# LED16_23.net
KiCad netlist of a schematic drawn in Altium Designer
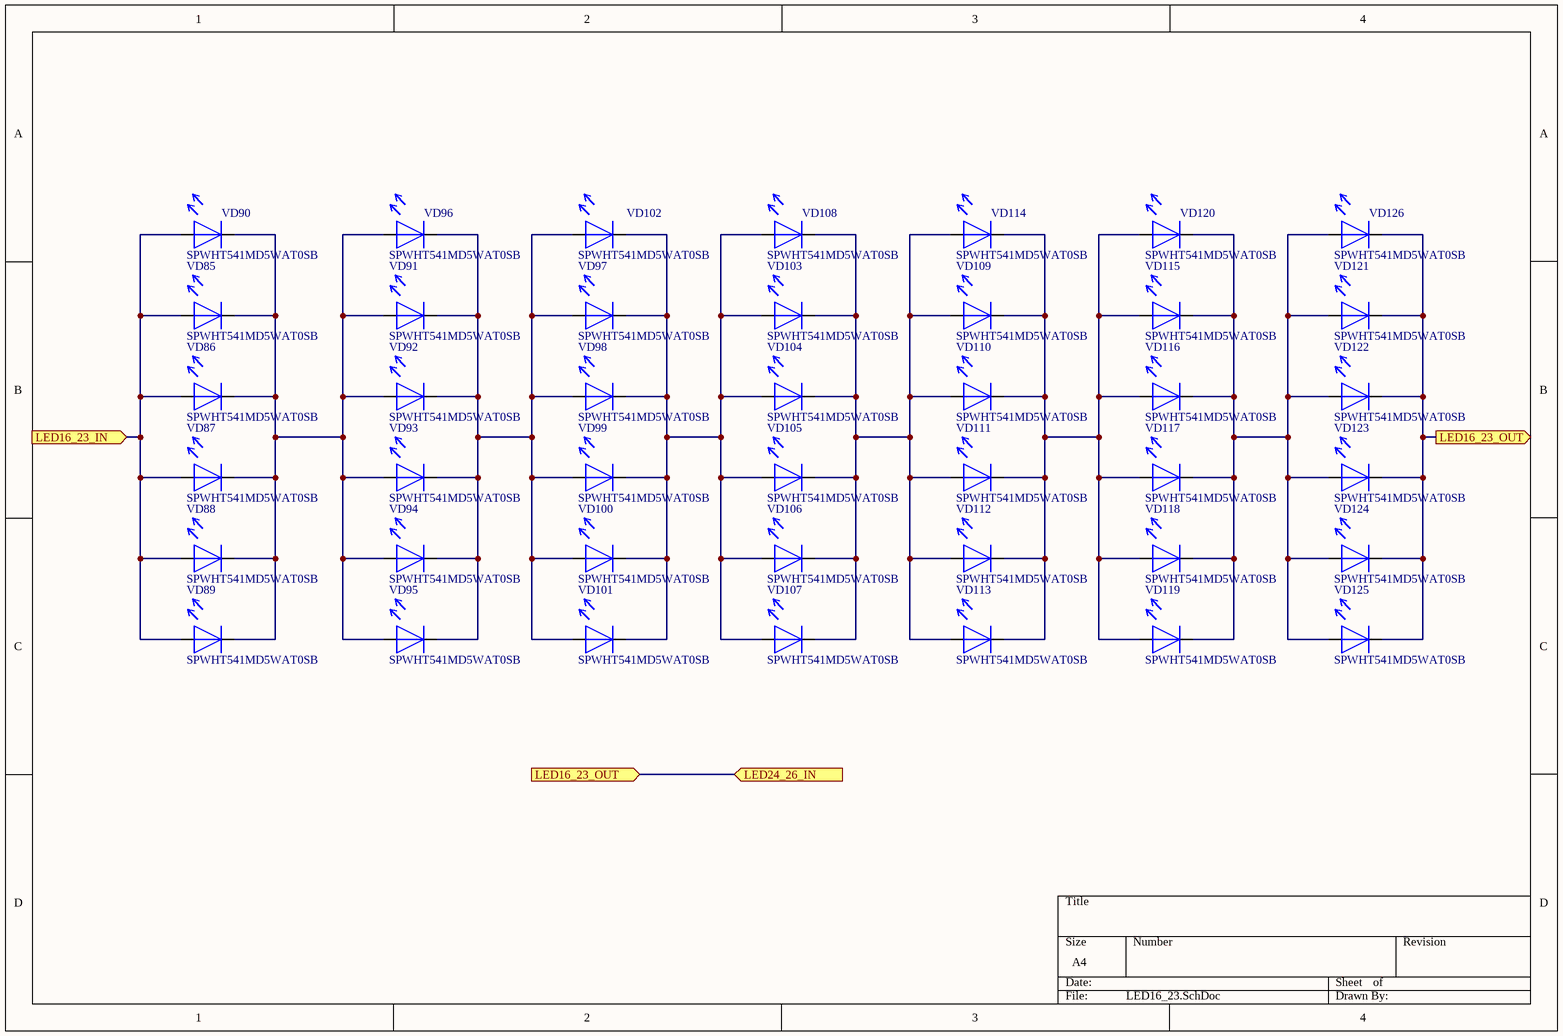
[diagram p0: LED16_23.SchDoc]

(export (version "E")
  (design (tool "Eeschema 10.0.6"))
  (components
    (comp (ref "VD85")
      (value "SPWHT541MD5WAT0SB")
      (footprint "LED_SAMSUNG")
      (libsource (lib "gprs_modem") (part "LED SPWHT541MD5WAT0SB"))
    )
    (comp (ref "VD86")
      (value "SPWHT541MD5WAT0SB")
      (footprint "LED_SAMSUNG")
      (libsource (lib "gprs_modem") (part "LED SPWHT541MD5WAT0SB"))
    )
    (comp (ref "VD87")
      (value "SPWHT541MD5WAT0SB")
      (footprint "LED_SAMSUNG")
      (libsource (lib "gprs_modem") (part "LED SPWHT541MD5WAT0SB"))
    )
    (comp (ref "VD88")
      (value "SPWHT541MD5WAT0SB")
      (footprint "LED_SAMSUNG")
      (libsource (lib "gprs_modem") (part "LED SPWHT541MD5WAT0SB"))
    )
    (comp (ref "VD89")
      (value "SPWHT541MD5WAT0SB")
      (footprint "LED_SAMSUNG")
      (libsource (lib "gprs_modem") (part "LED SPWHT541MD5WAT0SB"))
    )
    (comp (ref "VD90")
      (value "SPWHT541MD5WAT0SB")
      (footprint "LED_SAMSUNG")
      (libsource (lib "gprs_modem") (part "LED SPWHT541MD5WAT0SB"))
    )
    (comp (ref "VD91")
      (value "SPWHT541MD5WAT0SB")
      (footprint "LED_SAMSUNG")
      (libsource (lib "gprs_modem") (part "LED SPWHT541MD5WAT0SB"))
    )
    (comp (ref "VD92")
      (value "SPWHT541MD5WAT0SB")
      (footprint "LED_SAMSUNG")
      (libsource (lib "gprs_modem") (part "LED SPWHT541MD5WAT0SB"))
    )
    (comp (ref "VD93")
      (value "SPWHT541MD5WAT0SB")
      (footprint "LED_SAMSUNG")
      (libsource (lib "gprs_modem") (part "LED SPWHT541MD5WAT0SB"))
    )
    (comp (ref "VD94")
      (value "SPWHT541MD5WAT0SB")
      (footprint "LED_SAMSUNG")
      (libsource (lib "gprs_modem") (part "LED SPWHT541MD5WAT0SB"))
    )
    (comp (ref "VD95")
      (value "SPWHT541MD5WAT0SB")
      (footprint "LED_SAMSUNG")
      (libsource (lib "gprs_modem") (part "LED SPWHT541MD5WAT0SB"))
    )
    (comp (ref "VD96")
      (value "SPWHT541MD5WAT0SB")
      (footprint "LED_SAMSUNG")
      (libsource (lib "gprs_modem") (part "LED SPWHT541MD5WAT0SB"))
    )
    (comp (ref "VD97")
      (value "SPWHT541MD5WAT0SB")
      (footprint "LED_SAMSUNG")
      (libsource (lib "gprs_modem") (part "LED SPWHT541MD5WAT0SB"))
    )
    (comp (ref "VD98")
      (value "SPWHT541MD5WAT0SB")
      (footprint "LED_SAMSUNG")
      (libsource (lib "gprs_modem") (part "LED SPWHT541MD5WAT0SB"))
    )
    (comp (ref "VD99")
      (value "SPWHT541MD5WAT0SB")
      (footprint "LED_SAMSUNG")
      (libsource (lib "gprs_modem") (part "LED SPWHT541MD5WAT0SB"))
    )
    (comp (ref "VD100")
      (value "SPWHT541MD5WAT0SB")
      (footprint "LED_SAMSUNG")
      (libsource (lib "gprs_modem") (part "LED SPWHT541MD5WAT0SB"))
    )
    (comp (ref "VD101")
      (value "SPWHT541MD5WAT0SB")
      (footprint "LED_SAMSUNG")
      (libsource (lib "gprs_modem") (part "LED SPWHT541MD5WAT0SB"))
    )
    (comp (ref "VD102")
      (value "SPWHT541MD5WAT0SB")
      (footprint "LED_SAMSUNG")
      (libsource (lib "gprs_modem") (part "LED SPWHT541MD5WAT0SB"))
    )
    (comp (ref "VD103")
      (value "SPWHT541MD5WAT0SB")
      (footprint "LED_SAMSUNG")
      (libsource (lib "gprs_modem") (part "LED SPWHT541MD5WAT0SB"))
    )
    (comp (ref "VD104")
      (value "SPWHT541MD5WAT0SB")
      (footprint "LED_SAMSUNG")
      (libsource (lib "gprs_modem") (part "LED SPWHT541MD5WAT0SB"))
    )
    (comp (ref "VD105")
      (value "SPWHT541MD5WAT0SB")
      (footprint "LED_SAMSUNG")
      (libsource (lib "gprs_modem") (part "LED SPWHT541MD5WAT0SB"))
    )
    (comp (ref "VD106")
      (value "SPWHT541MD5WAT0SB")
      (footprint "LED_SAMSUNG")
      (libsource (lib "gprs_modem") (part "LED SPWHT541MD5WAT0SB"))
    )
    (comp (ref "VD107")
      (value "SPWHT541MD5WAT0SB")
      (footprint "LED_SAMSUNG")
      (libsource (lib "gprs_modem") (part "LED SPWHT541MD5WAT0SB"))
    )
    (comp (ref "VD108")
      (value "SPWHT541MD5WAT0SB")
      (footprint "LED_SAMSUNG")
      (libsource (lib "gprs_modem") (part "LED SPWHT541MD5WAT0SB"))
    )
    (comp (ref "VD109")
      (value "SPWHT541MD5WAT0SB")
      (footprint "LED_SAMSUNG")
      (libsource (lib "gprs_modem") (part "LED SPWHT541MD5WAT0SB"))
    )
    (comp (ref "VD110")
      (value "SPWHT541MD5WAT0SB")
      (footprint "LED_SAMSUNG")
      (libsource (lib "gprs_modem") (part "LED SPWHT541MD5WAT0SB"))
    )
    (comp (ref "VD111")
      (value "SPWHT541MD5WAT0SB")
      (footprint "LED_SAMSUNG")
      (libsource (lib "gprs_modem") (part "LED SPWHT541MD5WAT0SB"))
    )
    (comp (ref "VD112")
      (value "SPWHT541MD5WAT0SB")
      (footprint "LED_SAMSUNG")
      (libsource (lib "gprs_modem") (part "LED SPWHT541MD5WAT0SB"))
    )
    (comp (ref "VD113")
      (value "SPWHT541MD5WAT0SB")
      (footprint "LED_SAMSUNG")
      (libsource (lib "gprs_modem") (part "LED SPWHT541MD5WAT0SB"))
    )
    (comp (ref "VD114")
      (value "SPWHT541MD5WAT0SB")
      (footprint "LED_SAMSUNG")
      (libsource (lib "gprs_modem") (part "LED SPWHT541MD5WAT0SB"))
    )
    (comp (ref "VD115")
      (value "SPWHT541MD5WAT0SB")
      (footprint "LED_SAMSUNG")
      (libsource (lib "gprs_modem") (part "LED SPWHT541MD5WAT0SB"))
    )
    (comp (ref "VD116")
      (value "SPWHT541MD5WAT0SB")
      (footprint "LED_SAMSUNG")
      (libsource (lib "gprs_modem") (part "LED SPWHT541MD5WAT0SB"))
    )
    (comp (ref "VD117")
      (value "SPWHT541MD5WAT0SB")
      (footprint "LED_SAMSUNG")
      (libsource (lib "gprs_modem") (part "LED SPWHT541MD5WAT0SB"))
    )
    (comp (ref "VD118")
      (value "SPWHT541MD5WAT0SB")
      (footprint "LED_SAMSUNG")
      (libsource (lib "gprs_modem") (part "LED SPWHT541MD5WAT0SB"))
    )
    (comp (ref "VD119")
      (value "SPWHT541MD5WAT0SB")
      (footprint "LED_SAMSUNG")
      (libsource (lib "gprs_modem") (part "LED SPWHT541MD5WAT0SB"))
    )
    (comp (ref "VD120")
      (value "SPWHT541MD5WAT0SB")
      (footprint "LED_SAMSUNG")
      (libsource (lib "gprs_modem") (part "LED SPWHT541MD5WAT0SB"))
    )
    (comp (ref "VD121")
      (value "SPWHT541MD5WAT0SB")
      (footprint "LED_SAMSUNG")
      (libsource (lib "gprs_modem") (part "LED SPWHT541MD5WAT0SB"))
    )
    (comp (ref "VD122")
      (value "SPWHT541MD5WAT0SB")
      (footprint "LED_SAMSUNG")
      (libsource (lib "gprs_modem") (part "LED SPWHT541MD5WAT0SB"))
    )
    (comp (ref "VD123")
      (value "SPWHT541MD5WAT0SB")
      (footprint "LED_SAMSUNG")
      (libsource (lib "gprs_modem") (part "LED SPWHT541MD5WAT0SB"))
    )
    (comp (ref "VD124")
      (value "SPWHT541MD5WAT0SB")
      (footprint "LED_SAMSUNG")
      (libsource (lib "gprs_modem") (part "LED SPWHT541MD5WAT0SB"))
    )
    (comp (ref "VD125")
      (value "SPWHT541MD5WAT0SB")
      (footprint "LED_SAMSUNG")
      (libsource (lib "gprs_modem") (part "LED SPWHT541MD5WAT0SB"))
    )
    (comp (ref "VD126")
      (value "SPWHT541MD5WAT0SB")
      (footprint "LED_SAMSUNG")
      (libsource (lib "gprs_modem") (part "LED SPWHT541MD5WAT0SB"))
    )
  )
  (nets
    (net (code "1") (name "/LED16_23_IN") (class "Default")
      (node (ref "VD85") (pin "1") (pintype "passive"))
      (node (ref "VD86") (pin "1") (pintype "passive"))
      (node (ref "VD87") (pin "1") (pintype "passive"))
      (node (ref "VD88") (pin "1") (pintype "passive"))
      (node (ref "VD89") (pin "1") (pintype "passive"))
      (node (ref "VD90") (pin "1") (pintype "passive"))
    )
    (net (code "2") (name "/LED16_23_OUT") (class "Default")
      (node (ref "VD121") (pin "2") (pintype "passive"))
      (node (ref "VD122") (pin "2") (pintype "passive"))
      (node (ref "VD123") (pin "2") (pintype "passive"))
      (node (ref "VD124") (pin "2") (pintype "passive"))
      (node (ref "VD125") (pin "2") (pintype "passive"))
      (node (ref "VD126") (pin "2") (pintype "passive"))
    )
    (net (code "3") (name "Net-(VD85-Pad2)") (class "Default")
      (node (ref "VD85") (pin "2") (pintype "passive"))
      (node (ref "VD86") (pin "2") (pintype "passive"))
      (node (ref "VD87") (pin "2") (pintype "passive"))
      (node (ref "VD88") (pin "2") (pintype "passive"))
      (node (ref "VD89") (pin "2") (pintype "passive"))
      (node (ref "VD90") (pin "2") (pintype "passive"))
      (node (ref "VD91") (pin "1") (pintype "passive"))
      (node (ref "VD92") (pin "1") (pintype "passive"))
      (node (ref "VD93") (pin "1") (pintype "passive"))
      (node (ref "VD94") (pin "1") (pintype "passive"))
      (node (ref "VD95") (pin "1") (pintype "passive"))
      (node (ref "VD96") (pin "1") (pintype "passive"))
    )
    (net (code "4") (name "Net-(VD100-Pad1)") (class "Default")
      (node (ref "VD100") (pin "1") (pintype "passive"))
      (node (ref "VD101") (pin "1") (pintype "passive"))
      (node (ref "VD102") (pin "1") (pintype "passive"))
      (node (ref "VD91") (pin "2") (pintype "passive"))
      (node (ref "VD92") (pin "2") (pintype "passive"))
      (node (ref "VD93") (pin "2") (pintype "passive"))
      (node (ref "VD94") (pin "2") (pintype "passive"))
      (node (ref "VD95") (pin "2") (pintype "passive"))
      (node (ref "VD96") (pin "2") (pintype "passive"))
      (node (ref "VD97") (pin "1") (pintype "passive"))
      (node (ref "VD98") (pin "1") (pintype "passive"))
      (node (ref "VD99") (pin "1") (pintype "passive"))
    )
    (net (code "5") (name "Net-(VD100-Pad2)") (class "Default")
      (node (ref "VD100") (pin "2") (pintype "passive"))
      (node (ref "VD101") (pin "2") (pintype "passive"))
      (node (ref "VD102") (pin "2") (pintype "passive"))
      (node (ref "VD103") (pin "1") (pintype "passive"))
      (node (ref "VD104") (pin "1") (pintype "passive"))
      (node (ref "VD105") (pin "1") (pintype "passive"))
      (node (ref "VD106") (pin "1") (pintype "passive"))
      (node (ref "VD107") (pin "1") (pintype "passive"))
      (node (ref "VD108") (pin "1") (pintype "passive"))
      (node (ref "VD97") (pin "2") (pintype "passive"))
      (node (ref "VD98") (pin "2") (pintype "passive"))
      (node (ref "VD99") (pin "2") (pintype "passive"))
    )
    (net (code "6") (name "Net-(VD103-Pad2)") (class "Default")
      (node (ref "VD103") (pin "2") (pintype "passive"))
      (node (ref "VD104") (pin "2") (pintype "passive"))
      (node (ref "VD105") (pin "2") (pintype "passive"))
      (node (ref "VD106") (pin "2") (pintype "passive"))
      (node (ref "VD107") (pin "2") (pintype "passive"))
      (node (ref "VD108") (pin "2") (pintype "passive"))
      (node (ref "VD109") (pin "1") (pintype "passive"))
      (node (ref "VD110") (pin "1") (pintype "passive"))
      (node (ref "VD111") (pin "1") (pintype "passive"))
      (node (ref "VD112") (pin "1") (pintype "passive"))
      (node (ref "VD113") (pin "1") (pintype "passive"))
      (node (ref "VD114") (pin "1") (pintype "passive"))
    )
    (net (code "7") (name "Net-(VD109-Pad2)") (class "Default")
      (node (ref "VD109") (pin "2") (pintype "passive"))
      (node (ref "VD110") (pin "2") (pintype "passive"))
      (node (ref "VD111") (pin "2") (pintype "passive"))
      (node (ref "VD112") (pin "2") (pintype "passive"))
      (node (ref "VD113") (pin "2") (pintype "passive"))
      (node (ref "VD114") (pin "2") (pintype "passive"))
      (node (ref "VD115") (pin "1") (pintype "passive"))
      (node (ref "VD116") (pin "1") (pintype "passive"))
      (node (ref "VD117") (pin "1") (pintype "passive"))
      (node (ref "VD118") (pin "1") (pintype "passive"))
      (node (ref "VD119") (pin "1") (pintype "passive"))
      (node (ref "VD120") (pin "1") (pintype "passive"))
    )
    (net (code "8") (name "Net-(VD115-Pad2)") (class "Default")
      (node (ref "VD115") (pin "2") (pintype "passive"))
      (node (ref "VD116") (pin "2") (pintype "passive"))
      (node (ref "VD117") (pin "2") (pintype "passive"))
      (node (ref "VD118") (pin "2") (pintype "passive"))
      (node (ref "VD119") (pin "2") (pintype "passive"))
      (node (ref "VD120") (pin "2") (pintype "passive"))
      (node (ref "VD121") (pin "1") (pintype "passive"))
      (node (ref "VD122") (pin "1") (pintype "passive"))
      (node (ref "VD123") (pin "1") (pintype "passive"))
      (node (ref "VD124") (pin "1") (pintype "passive"))
      (node (ref "VD125") (pin "1") (pintype "passive"))
      (node (ref "VD126") (pin "1") (pintype "passive"))
    )
  )
)
